# zb_hub.net
KiCad netlist of a schematic drawn in Altium Designer
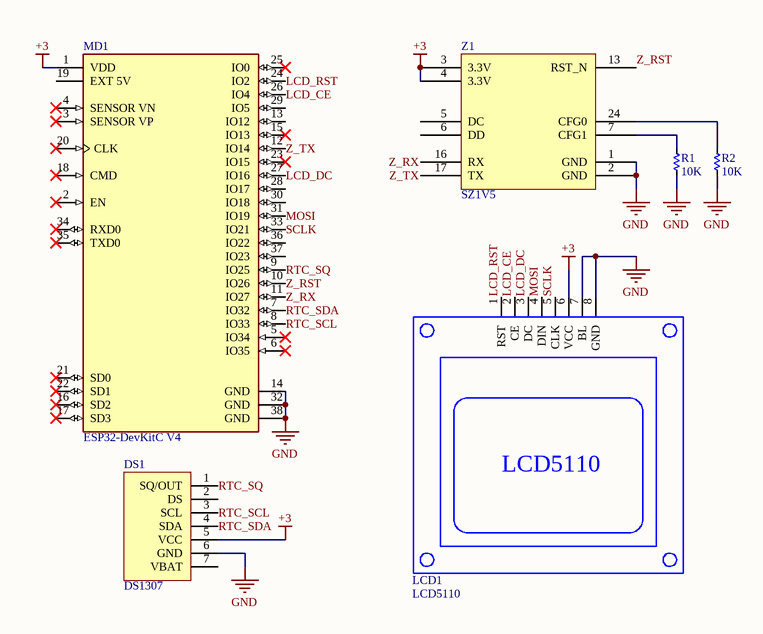
[diagram p0: zb_hub.SchDoc]

(export (version "E")
  (design (tool "Eeschema 10.0.6"))
  (components
    (comp (ref "DS1")
      (value "DS1307")
      (footprint "DS1307")
      (description "Tiny RTC I2C module DS1307")
      (libsource (lib "DS1307") (part "DS1307"))
    )
    (comp (ref "LCD1")
      (value "LCD5110")
      (footprint "LCD5110")
      (description "IC Philips PCD8544. 3V~5V, 84×48 pixels")
      (libsource (lib "LCD5110") (part "LCD5110"))
    )
    (comp (ref "MD1")
      (value "ESP32-DevKitC V4")
      (footprint "FP-ESP32-DevKitC_V4-MFG")
      (description "WiFi Development Tools (802.11) ESP32 General Development Kit, ESP32-WROOM-32 on the board")
      (fields
        (field (name "OCTOPART") "https://octopart.com/esp32-devkitc+v4-espressif+systems-107467262")
        (field (name "MANUFACTURER") "Espressif")
      )
      (libsource (lib "Altium Content Vault") (part "5ae961a1152c677524a60dea72d22f3"))
    )
    (comp (ref "R1")
      (value "10K")
      (footprint "RES-1/2W")
      (description "Res")
      (fields
        (field (name "MANUFACTURER") "Generic Components")
        (field (name "PUBLISHER") "Altium Hobart Technology Centre")
      )
      (libsource (lib "TechMT.VN_Lib_Project v2") (part "Res"))
    )
    (comp (ref "R2")
      (value "10K")
      (footprint "RES-1/2W")
      (description "Res")
      (fields
        (field (name "MANUFACTURER") "Generic Components")
        (field (name "PUBLISHER") "Altium Hobart Technology Centre")
      )
      (libsource (lib "TechMT.VN_Lib_Project v2") (part "Res"))
    )
    (comp (ref "Z1")
      (value "SZ1V5")
      (footprint "SZ1V5 PINOUT MODULE")
      (libsource (lib "SZ1V5") (part "SZ1V5_Alt"))
    )
  )
  (nets
    (net (code "1") (name "+3") (class "Default")
      (node (ref "DS1") (pin "5") (pinfunction "VCC_5") (pintype "passive"))
      (node (ref "LCD1") (pin "6") (pinfunction "VCC_6") (pintype "passive"))
      (node (ref "MD1") (pin "1") (pinfunction "VDD_1") (pintype "power_in"))
      (node (ref "Z1") (pin "3") (pinfunction "3.3V_3") (pintype "passive"))
      (node (ref "Z1") (pin "4") (pinfunction "3.3V_4") (pintype "passive"))
    )
    (net (code "2") (name "/LCD_CE") (class "Default")
      (node (ref "LCD1") (pin "2") (pinfunction "CE_2") (pintype "passive"))
      (node (ref "MD1") (pin "26") (pinfunction "IO4_26") (pintype "bidirectional"))
    )
    (net (code "3") (name "/LCD_DC") (class "Default")
      (node (ref "LCD1") (pin "3") (pinfunction "DC_3") (pintype "passive"))
      (node (ref "MD1") (pin "27") (pinfunction "IO16_27") (pintype "bidirectional"))
    )
    (net (code "4") (name "/LCD_RST") (class "Default")
      (node (ref "LCD1") (pin "1") (pinfunction "RST_1") (pintype "passive"))
      (node (ref "MD1") (pin "24") (pinfunction "IO2_24") (pintype "bidirectional"))
    )
    (net (code "5") (name "/MOSI") (class "Default")
      (node (ref "LCD1") (pin "4") (pinfunction "DIN_4") (pintype "passive"))
      (node (ref "MD1") (pin "31") (pinfunction "IO19_31") (pintype "bidirectional"))
    )
    (net (code "6") (name "/RTC_SCL") (class "Default")
      (node (ref "DS1") (pin "3") (pinfunction "SCL_3") (pintype "passive"))
      (node (ref "MD1") (pin "8") (pinfunction "IO33_8") (pintype "bidirectional"))
    )
    (net (code "7") (name "/RTC_SDA") (class "Default")
      (node (ref "DS1") (pin "4") (pinfunction "SDA_4") (pintype "passive"))
      (node (ref "MD1") (pin "7") (pinfunction "IO32_7") (pintype "bidirectional"))
    )
    (net (code "8") (name "/RTC_SQ") (class "Default")
      (node (ref "DS1") (pin "1") (pinfunction "SQ/OUT_1") (pintype "passive"))
      (node (ref "MD1") (pin "9") (pinfunction "IO25_9") (pintype "bidirectional"))
    )
    (net (code "9") (name "/SCLK") (class "Default")
      (node (ref "LCD1") (pin "5") (pinfunction "CLK_5") (pintype "passive"))
      (node (ref "MD1") (pin "33") (pinfunction "IO21_33") (pintype "bidirectional"))
    )
    (net (code "10") (name "/Z_RST") (class "Default")
      (node (ref "MD1") (pin "10") (pinfunction "IO26_10") (pintype "bidirectional"))
      (node (ref "Z1") (pin "13") (pinfunction "RST_N_13") (pintype "passive"))
    )
    (net (code "11") (name "/Z_RX") (class "Default")
      (node (ref "MD1") (pin "11") (pinfunction "IO27_11") (pintype "bidirectional"))
      (node (ref "Z1") (pin "16") (pinfunction "RX_16") (pintype "passive"))
    )
    (net (code "12") (name "/Z_TX") (class "Default")
      (node (ref "MD1") (pin "12") (pinfunction "IO14_12") (pintype "bidirectional"))
      (node (ref "Z1") (pin "17") (pinfunction "TX_17") (pintype "passive"))
    )
    (net (code "13") (name "GND") (class "Default")
      (node (ref "DS1") (pin "6") (pinfunction "GND_6") (pintype "passive"))
      (node (ref "LCD1") (pin "7") (pinfunction "BL_7") (pintype "passive"))
      (node (ref "LCD1") (pin "8") (pinfunction "GND_8") (pintype "passive"))
      (node (ref "MD1") (pin "14") (pinfunction "GND_14") (pintype "power_in"))
      (node (ref "MD1") (pin "32") (pinfunction "GND_32") (pintype "power_in"))
      (node (ref "MD1") (pin "38") (pinfunction "GND_38") (pintype "power_in"))
      (node (ref "R1") (pin "2") (pinfunction "2_2") (pintype "passive"))
      (node (ref "R2") (pin "2") (pinfunction "2_2") (pintype "passive"))
      (node (ref "Z1") (pin "1") (pinfunction "GND_1") (pintype "passive"))
      (node (ref "Z1") (pin "2") (pinfunction "GND_2") (pintype "passive"))
    )
    (net (code "14") (name "Net-(Z1-CFG0)") (class "Default")
      (node (ref "R2") (pin "1") (pinfunction "1_1") (pintype "passive"))
      (node (ref "Z1") (pin "24") (pinfunction "CFG0_24") (pintype "passive"))
    )
    (net (code "15") (name "Net-(Z1-CFG1)") (class "Default")
      (node (ref "R1") (pin "1") (pinfunction "1_1") (pintype "passive"))
      (node (ref "Z1") (pin "7") (pinfunction "CFG1_7") (pintype "passive"))
    )
    (net (code "16") (name "unconnected-(DS1-DS-Pad2)") (class "Default")
      (node (ref "DS1") (pin "2") (pinfunction "DS_2") (pintype "passive"))
    )
    (net (code "17") (name "unconnected-(DS1-VBAT-Pad7)") (class "Default")
      (node (ref "DS1") (pin "7") (pinfunction "VBAT_7") (pintype "passive"))
    )
    (net (code "18") (name "unconnected-(MD1-CLK-Pad20)") (class "Default")
      (node (ref "MD1") (pin "20") (pinfunction "CLK_20") (pintype "input+no_connect"))
    )
    (net (code "19") (name "unconnected-(MD1-CMD-Pad18)") (class "Default")
      (node (ref "MD1") (pin "18") (pinfunction "CMD_18") (pintype "input+no_connect"))
    )
    (net (code "20") (name "unconnected-(MD1-EN-Pad2)") (class "Default")
      (node (ref "MD1") (pin "2") (pinfunction "EN_2") (pintype "input+no_connect"))
    )
    (net (code "21") (name "unconnected-(MD1-EXT_5V-Pad19)") (class "Default")
      (node (ref "MD1") (pin "19") (pinfunction "EXT_5V_19") (pintype "power_in"))
    )
    (net (code "22") (name "unconnected-(MD1-IO0-Pad25)") (class "Default")
      (node (ref "MD1") (pin "25") (pinfunction "IO0_25") (pintype "bidirectional+no_connect"))
    )
    (net (code "23") (name "unconnected-(MD1-IO5-Pad29)") (class "Default")
      (node (ref "MD1") (pin "29") (pinfunction "IO5_29") (pintype "bidirectional"))
    )
    (net (code "24") (name "unconnected-(MD1-IO12-Pad13)") (class "Default")
      (node (ref "MD1") (pin "13") (pinfunction "IO12_13") (pintype "bidirectional"))
    )
    (net (code "25") (name "unconnected-(MD1-IO13-Pad15)") (class "Default")
      (node (ref "MD1") (pin "15") (pinfunction "IO13_15") (pintype "bidirectional+no_connect"))
    )
    (net (code "26") (name "unconnected-(MD1-IO15-Pad23)") (class "Default")
      (node (ref "MD1") (pin "23") (pinfunction "IO15_23") (pintype "bidirectional+no_connect"))
    )
    (net (code "27") (name "unconnected-(MD1-IO17-Pad28)") (class "Default")
      (node (ref "MD1") (pin "28") (pinfunction "IO17_28") (pintype "bidirectional"))
    )
    (net (code "28") (name "unconnected-(MD1-IO18-Pad30)") (class "Default")
      (node (ref "MD1") (pin "30") (pinfunction "IO18_30") (pintype "bidirectional"))
    )
    (net (code "29") (name "unconnected-(MD1-IO22-Pad36)") (class "Default")
      (node (ref "MD1") (pin "36") (pinfunction "IO22_36") (pintype "bidirectional"))
    )
    (net (code "30") (name "unconnected-(MD1-IO23-Pad37)") (class "Default")
      (node (ref "MD1") (pin "37") (pinfunction "IO23_37") (pintype "bidirectional"))
    )
    (net (code "31") (name "unconnected-(MD1-IO34-Pad5)") (class "Default")
      (node (ref "MD1") (pin "5") (pinfunction "IO34_5") (pintype "input+no_connect"))
    )
    (net (code "32") (name "unconnected-(MD1-IO35-Pad6)") (class "Default")
      (node (ref "MD1") (pin "6") (pinfunction "IO35_6") (pintype "input+no_connect"))
    )
    (net (code "33") (name "unconnected-(MD1-RXD0-Pad34)") (class "Default")
      (node (ref "MD1") (pin "34") (pinfunction "RXD0_34") (pintype "bidirectional+no_connect"))
    )
    (net (code "34") (name "unconnected-(MD1-SD0-Pad21)") (class "Default")
      (node (ref "MD1") (pin "21") (pinfunction "SD0_21") (pintype "bidirectional+no_connect"))
    )
    (net (code "35") (name "unconnected-(MD1-SD1-Pad22)") (class "Default")
      (node (ref "MD1") (pin "22") (pinfunction "SD1_22") (pintype "bidirectional+no_connect"))
    )
    (net (code "36") (name "unconnected-(MD1-SD2-Pad16)") (class "Default")
      (node (ref "MD1") (pin "16") (pinfunction "SD2_16") (pintype "bidirectional+no_connect"))
    )
    (net (code "37") (name "unconnected-(MD1-SD3-Pad17)") (class "Default")
      (node (ref "MD1") (pin "17") (pinfunction "SD3_17") (pintype "bidirectional+no_connect"))
    )
    (net (code "38") (name "unconnected-(MD1-SENSOR_VN-Pad4)") (class "Default")
      (node (ref "MD1") (pin "4") (pinfunction "SENSOR_VN_4") (pintype "input+no_connect"))
    )
    (net (code "39") (name "unconnected-(MD1-SENSOR_VP-Pad3)") (class "Default")
      (node (ref "MD1") (pin "3") (pinfunction "SENSOR_VP_3") (pintype "input+no_connect"))
    )
    (net (code "40") (name "unconnected-(MD1-TXD0-Pad35)") (class "Default")
      (node (ref "MD1") (pin "35") (pinfunction "TXD0_35") (pintype "bidirectional+no_connect"))
    )
    (net (code "41") (name "unconnected-(Z1-DC-Pad5)") (class "Default")
      (node (ref "Z1") (pin "5") (pinfunction "DC_5") (pintype "passive"))
    )
    (net (code "42") (name "unconnected-(Z1-DD-Pad6)") (class "Default")
      (node (ref "Z1") (pin "6") (pinfunction "DD_6") (pintype "passive"))
    )
  )
)
